# dice_3_1.net
KiCad netlist of a schematic drawn in EAGLE
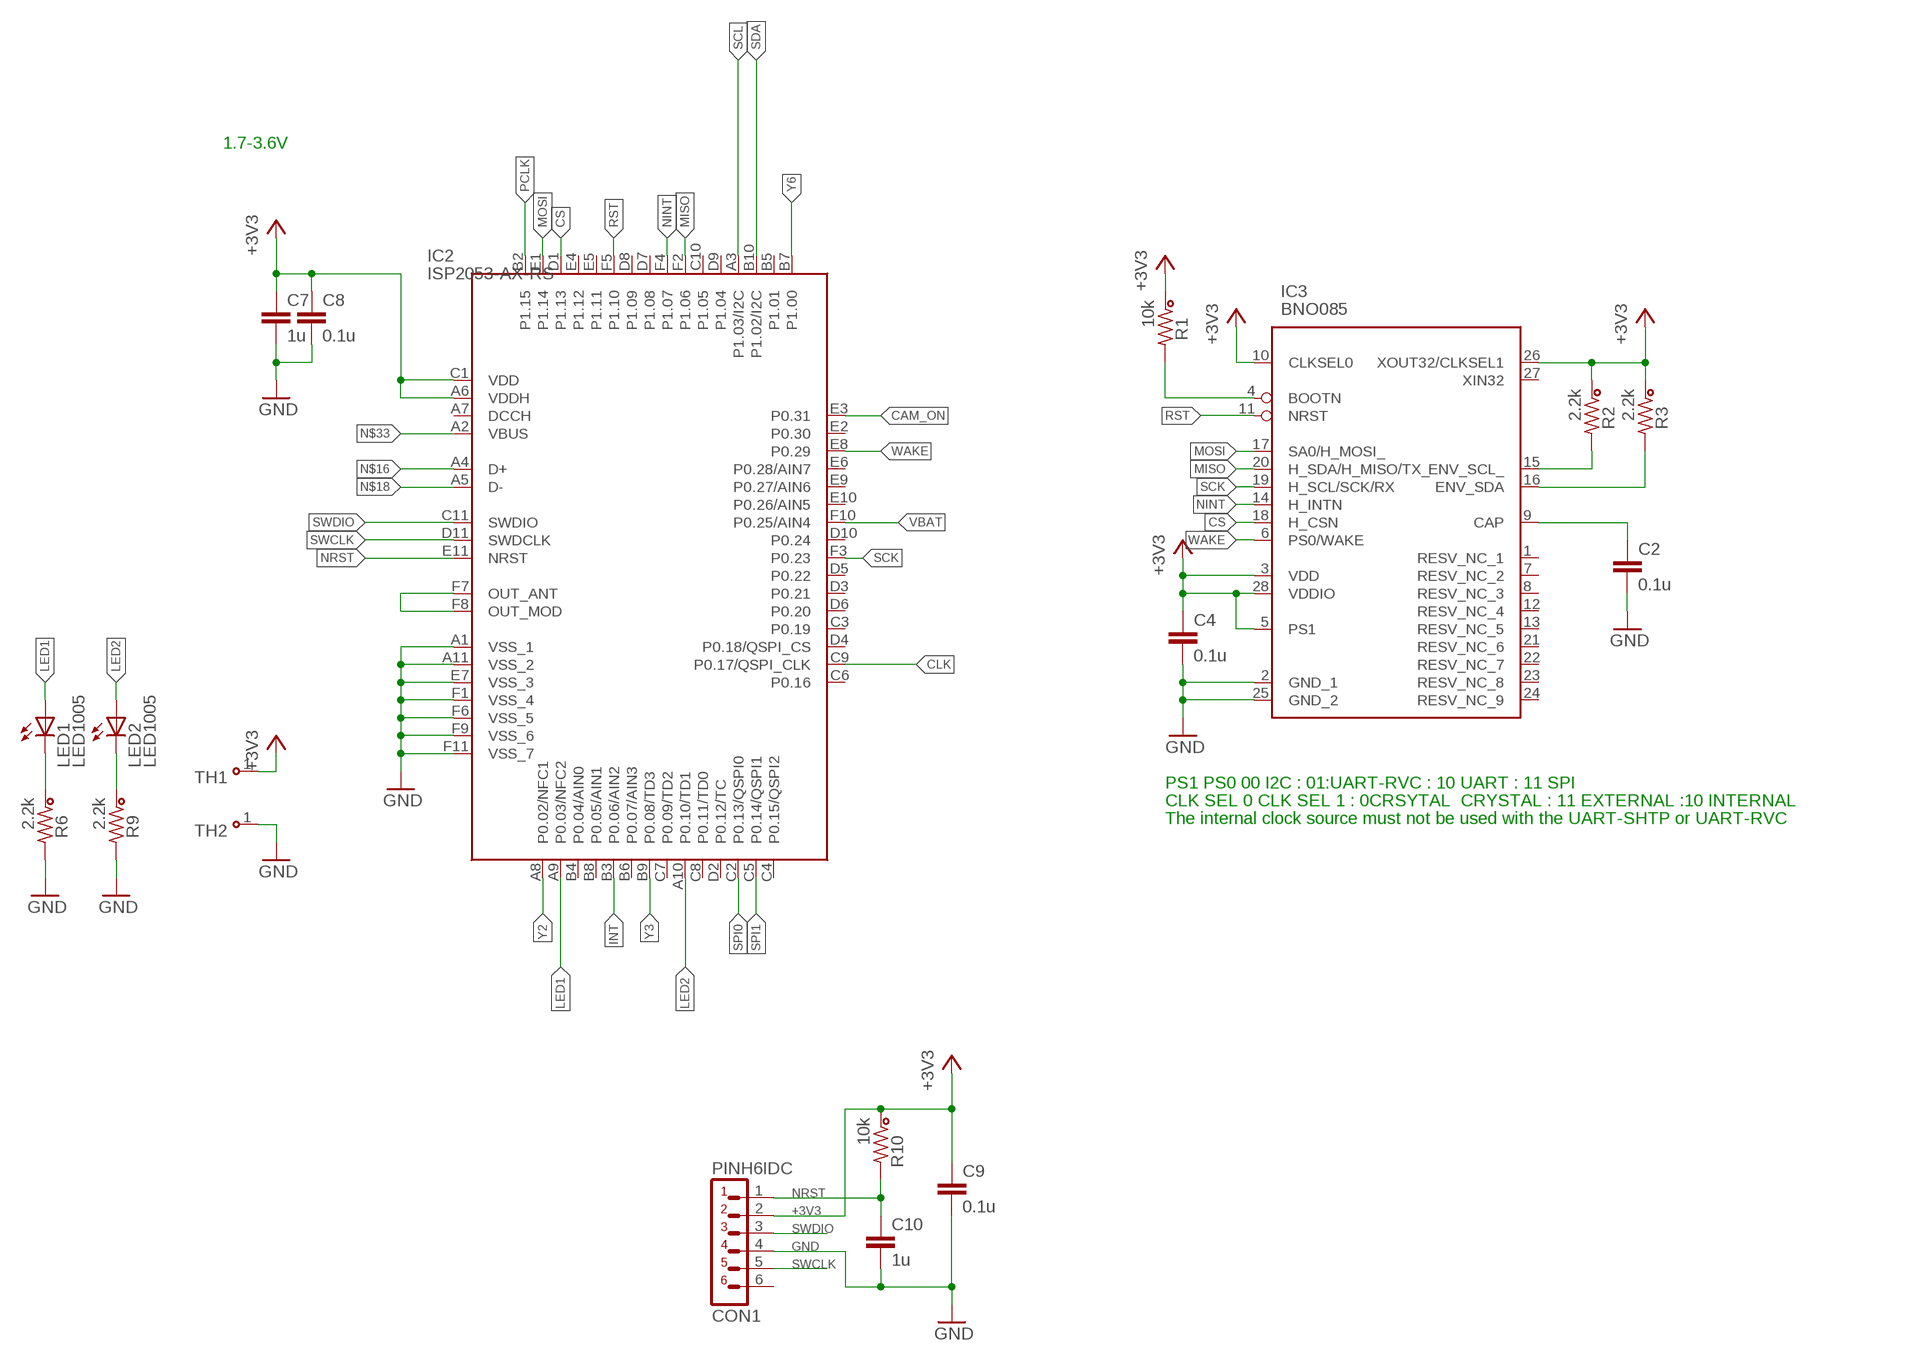
[diagram p0: schematic, sheet 1]

(export (version "E")
  (design (tool "Eeschema 10.0.6"))
  (components
    (comp (ref "C2")
      (value "0.1u")
      (footprint "eagle-import:1005K")
      (libsource (lib "eagle-import") (part "C-CC1005K"))
    )
    (comp (ref "C4")
      (value "0.1u")
      (footprint "eagle-import:1005K")
      (libsource (lib "eagle-import") (part "C-CC1005K"))
    )
    (comp (ref "C7")
      (value "1u")
      (footprint "eagle-import:1005K")
      (libsource (lib "eagle-import") (part "C-CC1005K"))
    )
    (comp (ref "C8")
      (value "0.1u")
      (footprint "eagle-import:1005K")
      (libsource (lib "eagle-import") (part "C-CC1005K"))
    )
    (comp (ref "C9")
      (value "0.1u")
      (footprint "eagle-import:1005K")
      (libsource (lib "eagle-import") (part "C-CC1005K"))
    )
    (comp (ref "C10")
      (value "1u")
      (footprint "eagle-import:1005K")
      (libsource (lib "eagle-import") (part "C-CC1005K"))
    )
    (comp (ref "CON1")
      (value "PINH6IDC")
      (footprint "eagle-import:1X6IDC_1R27")
      (libsource (lib "eagle-import") (part "PINH6IDC"))
    )
    (comp (ref "IC2")
      (value "ISP2053-AX-RS")
      (footprint "eagle-import:ISP2053AXRS")
      (fields (field (name "MOUSER_PART_NUMBER") "359-ISP2053-AX-RS"))
      (libsource (lib "eagle-import") (part "ISP2053-AX-RS"))
    )
    (comp (ref "IC3")
      (value "BNO085")
      (footprint "eagle-import:BNO085")
      (fields (field (name "MOUSER_PART_NUMBER") "526-BNO085"))
      (libsource (lib "eagle-import") (part "BNO085"))
    )
    (comp (ref "LED1")
      (value "LED1005")
      (footprint "eagle-import:1005K-LED")
      (libsource (lib "eagle-import") (part "LED1005"))
    )
    (comp (ref "LED2")
      (value "LED1005")
      (footprint "eagle-import:1005K-LED")
      (libsource (lib "eagle-import") (part "LED1005"))
    )
    (comp (ref "R1")
      (value "10k")
      (footprint "eagle-import:1005K")
      (libsource (lib "eagle-import") (part "R-CC1005K"))
    )
    (comp (ref "R2")
      (value "2.2k")
      (footprint "eagle-import:1005K")
      (libsource (lib "eagle-import") (part "R-CC1005K"))
    )
    (comp (ref "R3")
      (value "2.2k")
      (footprint "eagle-import:1005K")
      (libsource (lib "eagle-import") (part "R-CC1005K"))
    )
    (comp (ref "R6")
      (value "2.2k")
      (footprint "eagle-import:1005K")
      (libsource (lib "eagle-import") (part "R-CC1005K"))
    )
    (comp (ref "R9")
      (value "2.2k")
      (footprint "eagle-import:1005K")
      (libsource (lib "eagle-import") (part "R-CC1005K"))
    )
    (comp (ref "R10")
      (value "10k")
      (footprint "eagle-import:1005K")
      (libsource (lib "eagle-import") (part "R-CC1005K"))
    )
    (comp (ref "TH1")
      (value "THCHK")
      (footprint "eagle-import:03C")
      (libsource (lib "eagle-import") (part "THCHK"))
    )
    (comp (ref "TH2")
      (value "THCHK")
      (footprint "eagle-import:03C")
      (libsource (lib "eagle-import") (part "THCHK"))
    )
  )
  (nets
    (net (code "1") (name "+3V3") (class "Default")
      (node (ref "C4") (pin "1") (pinfunction "1_1") (pintype "passive"))
      (node (ref "C7") (pin "1") (pinfunction "1_1") (pintype "passive"))
      (node (ref "C8") (pin "1") (pinfunction "1_1") (pintype "passive"))
      (node (ref "C9") (pin "1") (pinfunction "1_1") (pintype "passive"))
      (node (ref "CON1") (pin "2") (pinfunction "2_2") (pintype "passive"))
      (node (ref "IC2") (pin "A6") (pinfunction "VDDH_A6") (pintype "bidirectional"))
      (node (ref "IC2") (pin "C1") (pinfunction "VDD_C1") (pintype "bidirectional"))
      (node (ref "IC3") (pin "10") (pinfunction "CLKSEL0_10") (pintype "bidirectional"))
      (node (ref "IC3") (pin "26") (pinfunction "XOUT32/CLKSEL1_26") (pintype "bidirectional"))
      (node (ref "IC3") (pin "28") (pinfunction "VDDIO_28") (pintype "bidirectional"))
      (node (ref "IC3") (pin "3") (pinfunction "VDD_3") (pintype "bidirectional"))
      (node (ref "IC3") (pin "5") (pinfunction "PS1_5") (pintype "bidirectional"))
      (node (ref "R1") (pin "1") (pinfunction "1_1") (pintype "passive"))
      (node (ref "R10") (pin "1") (pinfunction "1_1") (pintype "passive"))
      (node (ref "R2") (pin "1") (pinfunction "1_1") (pintype "passive"))
      (node (ref "R3") (pin "1") (pinfunction "1_1") (pintype "passive"))
      (node (ref "TH1") (pin "1") (pinfunction "1_1") (pintype "passive"))
    )
    (net (code "2") (name "CAM_ON") (class "Default")
      (node (ref "IC2") (pin "E3") (pinfunction "P0.31_E3") (pintype "bidirectional"))
    )
    (net (code "3") (name "CLK") (class "Default")
      (node (ref "IC2") (pin "C9") (pinfunction "P0.17/QSPI_CLK_C9") (pintype "bidirectional"))
    )
    (net (code "4") (name "CS") (class "Default")
      (node (ref "IC2") (pin "D1") (pinfunction "P1.13_D1") (pintype "bidirectional"))
      (node (ref "IC3") (pin "18") (pinfunction "H_CSN_18") (pintype "bidirectional"))
    )
    (net (code "5") (name "GND") (class "Default")
      (node (ref "C10") (pin "2") (pinfunction "2_2") (pintype "passive"))
      (node (ref "C2") (pin "2") (pinfunction "2_2") (pintype "passive"))
      (node (ref "C4") (pin "2") (pinfunction "2_2") (pintype "passive"))
      (node (ref "C7") (pin "2") (pinfunction "2_2") (pintype "passive"))
      (node (ref "C8") (pin "2") (pinfunction "2_2") (pintype "passive"))
      (node (ref "C9") (pin "2") (pinfunction "2_2") (pintype "passive"))
      (node (ref "CON1") (pin "4") (pinfunction "4_4") (pintype "passive"))
      (node (ref "IC2") (pin "A1") (pinfunction "VSS_1_A1") (pintype "bidirectional"))
      (node (ref "IC2") (pin "A11") (pinfunction "VSS_2_A11") (pintype "bidirectional"))
      (node (ref "IC2") (pin "E7") (pinfunction "VSS_3_E7") (pintype "bidirectional"))
      (node (ref "IC2") (pin "F1") (pinfunction "VSS_4_F1") (pintype "bidirectional"))
      (node (ref "IC2") (pin "F11") (pinfunction "VSS_7_F11") (pintype "bidirectional"))
      (node (ref "IC2") (pin "F6") (pinfunction "VSS_5_F6") (pintype "bidirectional"))
      (node (ref "IC2") (pin "F9") (pinfunction "VSS_6_F9") (pintype "bidirectional"))
      (node (ref "IC3") (pin "2") (pinfunction "GND_1_2") (pintype "bidirectional"))
      (node (ref "IC3") (pin "25") (pinfunction "GND_2_25") (pintype "bidirectional"))
      (node (ref "R6") (pin "2") (pinfunction "2_2") (pintype "passive"))
      (node (ref "R9") (pin "2") (pinfunction "2_2") (pintype "passive"))
      (node (ref "TH2") (pin "1") (pinfunction "1_1") (pintype "passive"))
    )
    (net (code "6") (name "INT") (class "Default")
      (node (ref "IC2") (pin "B3") (pinfunction "P0.06/AIN2_B3") (pintype "bidirectional"))
    )
    (net (code "7") (name "LED1") (class "Default")
      (node (ref "IC2") (pin "A9") (pinfunction "P0.03/NFC2_A9") (pintype "bidirectional"))
      (node (ref "LED1") (pin "A") (pinfunction "A_A") (pintype "passive"))
    )
    (net (code "8") (name "LED2") (class "Default")
      (node (ref "IC2") (pin "A10") (pinfunction "P0.10/TD1_A10") (pintype "bidirectional"))
      (node (ref "LED2") (pin "A") (pinfunction "A_A") (pintype "passive"))
    )
    (net (code "9") (name "MISO") (class "Default")
      (node (ref "IC2") (pin "F2") (pinfunction "P1.06_F2") (pintype "bidirectional"))
      (node (ref "IC3") (pin "20") (pinfunction "H_SDA/H_MISO/TX__20") (pintype "bidirectional"))
    )
    (net (code "10") (name "MOSI") (class "Default")
      (node (ref "IC2") (pin "E1") (pinfunction "P1.14_E1") (pintype "bidirectional"))
      (node (ref "IC3") (pin "17") (pinfunction "SA0/H_MOSI__17") (pintype "bidirectional"))
    )
    (net (code "11") (name "N$16") (class "Default")
      (node (ref "IC2") (pin "A4") (pinfunction "D+_A4") (pintype "bidirectional"))
    )
    (net (code "12") (name "N$18") (class "Default")
      (node (ref "IC2") (pin "A5") (pinfunction "D-_A5") (pintype "bidirectional"))
    )
    (net (code "13") (name "N$33") (class "Default")
      (node (ref "IC2") (pin "A2") (pinfunction "VBUS_A2") (pintype "bidirectional"))
    )
    (net (code "14") (name "NINT") (class "Default")
      (node (ref "IC2") (pin "F4") (pinfunction "P1.07_F4") (pintype "bidirectional"))
      (node (ref "IC3") (pin "14") (pinfunction "H_INTN_14") (pintype "bidirectional"))
    )
    (net (code "15") (name "NRST") (class "Default")
      (node (ref "C10") (pin "1") (pinfunction "1_1") (pintype "passive"))
      (node (ref "CON1") (pin "1") (pinfunction "1_1") (pintype "passive"))
      (node (ref "IC2") (pin "E11") (pinfunction "NRST_E11") (pintype "bidirectional"))
      (node (ref "R10") (pin "2") (pinfunction "2_2") (pintype "passive"))
    )
    (net (code "16") (name "Net-(IC2-OUT_ANT)") (class "Default")
      (node (ref "IC2") (pin "F7") (pinfunction "OUT_ANT_F7") (pintype "bidirectional"))
      (node (ref "IC2") (pin "F8") (pinfunction "OUT_MOD_F8") (pintype "bidirectional"))
    )
    (net (code "17") (name "Net-(IC3-BOOTN)") (class "Default")
      (node (ref "IC3") (pin "4") (pinfunction "BOOTN_4") (pintype "bidirectional"))
      (node (ref "R1") (pin "2") (pinfunction "2_2") (pintype "passive"))
    )
    (net (code "18") (name "Net-(IC3-CAP)") (class "Default")
      (node (ref "C2") (pin "1") (pinfunction "1_1") (pintype "passive"))
      (node (ref "IC3") (pin "9") (pinfunction "CAP_9") (pintype "bidirectional"))
    )
    (net (code "19") (name "Net-(IC3-ENV_SCL_)") (class "Default")
      (node (ref "IC3") (pin "15") (pinfunction "ENV_SCL__15") (pintype "bidirectional"))
      (node (ref "R2") (pin "2") (pinfunction "2_2") (pintype "passive"))
    )
    (net (code "20") (name "Net-(IC3-ENV_SDA)") (class "Default")
      (node (ref "IC3") (pin "16") (pinfunction "ENV_SDA_16") (pintype "bidirectional"))
      (node (ref "R3") (pin "2") (pinfunction "2_2") (pintype "passive"))
    )
    (net (code "21") (name "Net-(LED1-C)") (class "Default")
      (node (ref "LED1") (pin "K") (pinfunction "C_K") (pintype "passive"))
      (node (ref "R6") (pin "1") (pinfunction "1_1") (pintype "passive"))
    )
    (net (code "22") (name "Net-(LED2-C)") (class "Default")
      (node (ref "LED2") (pin "K") (pinfunction "C_K") (pintype "passive"))
      (node (ref "R9") (pin "1") (pinfunction "1_1") (pintype "passive"))
    )
    (net (code "23") (name "PCLK") (class "Default")
      (node (ref "IC2") (pin "B2") (pinfunction "P1.15_B2") (pintype "bidirectional"))
    )
    (net (code "24") (name "RST") (class "Default")
      (node (ref "IC2") (pin "F5") (pinfunction "P1.10_F5") (pintype "bidirectional"))
      (node (ref "IC3") (pin "11") (pinfunction "NRST_11") (pintype "bidirectional"))
    )
    (net (code "25") (name "SCK") (class "Default")
      (node (ref "IC2") (pin "F3") (pinfunction "P0.23_F3") (pintype "bidirectional"))
      (node (ref "IC3") (pin "19") (pinfunction "H_SCL/SCK/RX_19") (pintype "bidirectional"))
    )
    (net (code "26") (name "SCL") (class "Default")
      (node (ref "IC2") (pin "A3") (pinfunction "P1.03/I2C_A3") (pintype "bidirectional"))
    )
    (net (code "27") (name "SDA") (class "Default")
      (node (ref "IC2") (pin "B10") (pinfunction "P1.02/I2C_B10") (pintype "bidirectional"))
    )
    (net (code "28") (name "SPI0") (class "Default")
      (node (ref "IC2") (pin "C2") (pinfunction "P0.13/QSPI0_C2") (pintype "bidirectional"))
    )
    (net (code "29") (name "SPI1") (class "Default")
      (node (ref "IC2") (pin "C5") (pinfunction "P0.14/QSPI1_C5") (pintype "bidirectional"))
    )
    (net (code "30") (name "SWCLK") (class "Default")
      (node (ref "CON1") (pin "5") (pinfunction "5_5") (pintype "passive"))
      (node (ref "IC2") (pin "D11") (pinfunction "SWDCLK_D11") (pintype "bidirectional"))
    )
    (net (code "31") (name "SWDIO") (class "Default")
      (node (ref "CON1") (pin "3") (pinfunction "3_3") (pintype "passive"))
      (node (ref "IC2") (pin "C11") (pinfunction "SWDIO_C11") (pintype "bidirectional"))
    )
    (net (code "32") (name "VBAT") (class "Default")
      (node (ref "IC2") (pin "F10") (pinfunction "P0.25/AIN4_F10") (pintype "bidirectional"))
    )
    (net (code "33") (name "WAKE") (class "Default")
      (node (ref "IC2") (pin "E8") (pinfunction "P0.29_E8") (pintype "bidirectional"))
      (node (ref "IC3") (pin "6") (pinfunction "PS0/WAKE_6") (pintype "bidirectional"))
    )
    (net (code "34") (name "Y2") (class "Default")
      (node (ref "IC2") (pin "A8") (pinfunction "P0.02/NFC1_A8") (pintype "bidirectional"))
    )
    (net (code "35") (name "Y3") (class "Default")
      (node (ref "IC2") (pin "B9") (pinfunction "P0.08/TD3_B9") (pintype "bidirectional"))
    )
    (net (code "36") (name "Y6") (class "Default")
      (node (ref "IC2") (pin "B7") (pinfunction "P1.00_B7") (pintype "bidirectional"))
    )
    (net (code "37") (name "unconnected-(CON1-Pad6)") (class "Default")
      (node (ref "CON1") (pin "6") (pinfunction "6_6") (pintype "passive"))
    )
    (net (code "38") (name "unconnected-(IC2-DCCH-PadA7)") (class "Default")
      (node (ref "IC2") (pin "A7") (pinfunction "DCCH_A7") (pintype "bidirectional"))
    )
    (net (code "39") (name "unconnected-(IC2-P0.04{slash}AIN0-PadB4)") (class "Default")
      (node (ref "IC2") (pin "B4") (pinfunction "P0.04/AIN0_B4") (pintype "bidirectional"))
    )
    (net (code "40") (name "unconnected-(IC2-P0.05{slash}AIN1-PadB8)") (class "Default")
      (node (ref "IC2") (pin "B8") (pinfunction "P0.05/AIN1_B8") (pintype "bidirectional"))
    )
    (net (code "41") (name "unconnected-(IC2-P0.07{slash}AIN3-PadB6)") (class "Default")
      (node (ref "IC2") (pin "B6") (pinfunction "P0.07/AIN3_B6") (pintype "bidirectional"))
    )
    (net (code "42") (name "unconnected-(IC2-P0.09{slash}TD2-PadC7)") (class "Default")
      (node (ref "IC2") (pin "C7") (pinfunction "P0.09/TD2_C7") (pintype "bidirectional"))
    )
    (net (code "43") (name "unconnected-(IC2-P0.11{slash}TD0-PadC8)") (class "Default")
      (node (ref "IC2") (pin "C8") (pinfunction "P0.11/TD0_C8") (pintype "bidirectional"))
    )
    (net (code "44") (name "unconnected-(IC2-P0.12{slash}TC-PadD2)") (class "Default")
      (node (ref "IC2") (pin "D2") (pinfunction "P0.12/TC_D2") (pintype "bidirectional"))
    )
    (net (code "45") (name "unconnected-(IC2-P0.15{slash}QSPI2-PadC4)") (class "Default")
      (node (ref "IC2") (pin "C4") (pinfunction "P0.15/QSPI2_C4") (pintype "bidirectional"))
    )
    (net (code "46") (name "unconnected-(IC2-P0.16-PadC6)") (class "Default")
      (node (ref "IC2") (pin "C6") (pinfunction "P0.16_C6") (pintype "bidirectional"))
    )
    (net (code "47") (name "unconnected-(IC2-P0.18{slash}QSPI_CS-PadD4)") (class "Default")
      (node (ref "IC2") (pin "D4") (pinfunction "P0.18/QSPI_CS_D4") (pintype "bidirectional"))
    )
    (net (code "48") (name "unconnected-(IC2-P0.19-PadC3)") (class "Default")
      (node (ref "IC2") (pin "C3") (pinfunction "P0.19_C3") (pintype "bidirectional"))
    )
    (net (code "49") (name "unconnected-(IC2-P0.20-PadD6)") (class "Default")
      (node (ref "IC2") (pin "D6") (pinfunction "P0.20_D6") (pintype "bidirectional"))
    )
    (net (code "50") (name "unconnected-(IC2-P0.21-PadD3)") (class "Default")
      (node (ref "IC2") (pin "D3") (pinfunction "P0.21_D3") (pintype "bidirectional"))
    )
    (net (code "51") (name "unconnected-(IC2-P0.22-PadD5)") (class "Default")
      (node (ref "IC2") (pin "D5") (pinfunction "P0.22_D5") (pintype "bidirectional"))
    )
    (net (code "52") (name "unconnected-(IC2-P0.24-PadD10)") (class "Default")
      (node (ref "IC2") (pin "D10") (pinfunction "P0.24_D10") (pintype "bidirectional"))
    )
    (net (code "53") (name "unconnected-(IC2-P0.26{slash}AIN5-PadE10)") (class "Default")
      (node (ref "IC2") (pin "E10") (pinfunction "P0.26/AIN5_E10") (pintype "bidirectional"))
    )
    (net (code "54") (name "unconnected-(IC2-P0.27{slash}AIN6-PadE9)") (class "Default")
      (node (ref "IC2") (pin "E9") (pinfunction "P0.27/AIN6_E9") (pintype "bidirectional"))
    )
    (net (code "55") (name "unconnected-(IC2-P0.28{slash}AIN7-PadE6)") (class "Default")
      (node (ref "IC2") (pin "E6") (pinfunction "P0.28/AIN7_E6") (pintype "bidirectional"))
    )
    (net (code "56") (name "unconnected-(IC2-P0.30-PadE2)") (class "Default")
      (node (ref "IC2") (pin "E2") (pinfunction "P0.30_E2") (pintype "bidirectional"))
    )
    (net (code "57") (name "unconnected-(IC2-P1.01-PadB5)") (class "Default")
      (node (ref "IC2") (pin "B5") (pinfunction "P1.01_B5") (pintype "bidirectional"))
    )
    (net (code "58") (name "unconnected-(IC2-P1.04-PadD9)") (class "Default")
      (node (ref "IC2") (pin "D9") (pinfunction "P1.04_D9") (pintype "bidirectional"))
    )
    (net (code "59") (name "unconnected-(IC2-P1.05-PadC10)") (class "Default")
      (node (ref "IC2") (pin "C10") (pinfunction "P1.05_C10") (pintype "bidirectional"))
    )
    (net (code "60") (name "unconnected-(IC2-P1.08-PadD7)") (class "Default")
      (node (ref "IC2") (pin "D7") (pinfunction "P1.08_D7") (pintype "bidirectional"))
    )
    (net (code "61") (name "unconnected-(IC2-P1.09-PadD8)") (class "Default")
      (node (ref "IC2") (pin "D8") (pinfunction "P1.09_D8") (pintype "bidirectional"))
    )
    (net (code "62") (name "unconnected-(IC2-P1.11-PadE5)") (class "Default")
      (node (ref "IC2") (pin "E5") (pinfunction "P1.11_E5") (pintype "bidirectional"))
    )
    (net (code "63") (name "unconnected-(IC2-P1.12-PadE4)") (class "Default")
      (node (ref "IC2") (pin "E4") (pinfunction "P1.12_E4") (pintype "bidirectional"))
    )
    (net (code "64") (name "unconnected-(IC3-RESV_NC_1-Pad1)") (class "Default")
      (node (ref "IC3") (pin "1") (pinfunction "RESV_NC_1_1") (pintype "bidirectional"))
    )
    (net (code "65") (name "unconnected-(IC3-RESV_NC_2-Pad7)") (class "Default")
      (node (ref "IC3") (pin "7") (pinfunction "RESV_NC_2_7") (pintype "bidirectional"))
    )
    (net (code "66") (name "unconnected-(IC3-RESV_NC_3-Pad8)") (class "Default")
      (node (ref "IC3") (pin "8") (pinfunction "RESV_NC_3_8") (pintype "bidirectional"))
    )
    (net (code "67") (name "unconnected-(IC3-RESV_NC_4-Pad12)") (class "Default")
      (node (ref "IC3") (pin "12") (pinfunction "RESV_NC_4_12") (pintype "bidirectional"))
    )
    (net (code "68") (name "unconnected-(IC3-RESV_NC_5-Pad13)") (class "Default")
      (node (ref "IC3") (pin "13") (pinfunction "RESV_NC_5_13") (pintype "bidirectional"))
    )
    (net (code "69") (name "unconnected-(IC3-RESV_NC_6-Pad21)") (class "Default")
      (node (ref "IC3") (pin "21") (pinfunction "RESV_NC_6_21") (pintype "bidirectional"))
    )
    (net (code "70") (name "unconnected-(IC3-RESV_NC_7-Pad22)") (class "Default")
      (node (ref "IC3") (pin "22") (pinfunction "RESV_NC_7_22") (pintype "bidirectional"))
    )
    (net (code "71") (name "unconnected-(IC3-RESV_NC_8-Pad23)") (class "Default")
      (node (ref "IC3") (pin "23") (pinfunction "RESV_NC_8_23") (pintype "bidirectional"))
    )
    (net (code "72") (name "unconnected-(IC3-RESV_NC_9-Pad24)") (class "Default")
      (node (ref "IC3") (pin "24") (pinfunction "RESV_NC_9_24") (pintype "bidirectional"))
    )
    (net (code "73") (name "unconnected-(IC3-XIN32-Pad27)") (class "Default")
      (node (ref "IC3") (pin "27") (pinfunction "XIN32_27") (pintype "bidirectional"))
    )
  )
)
